# Peripherals.net
KiCad netlist of a schematic drawn in Altium Designer
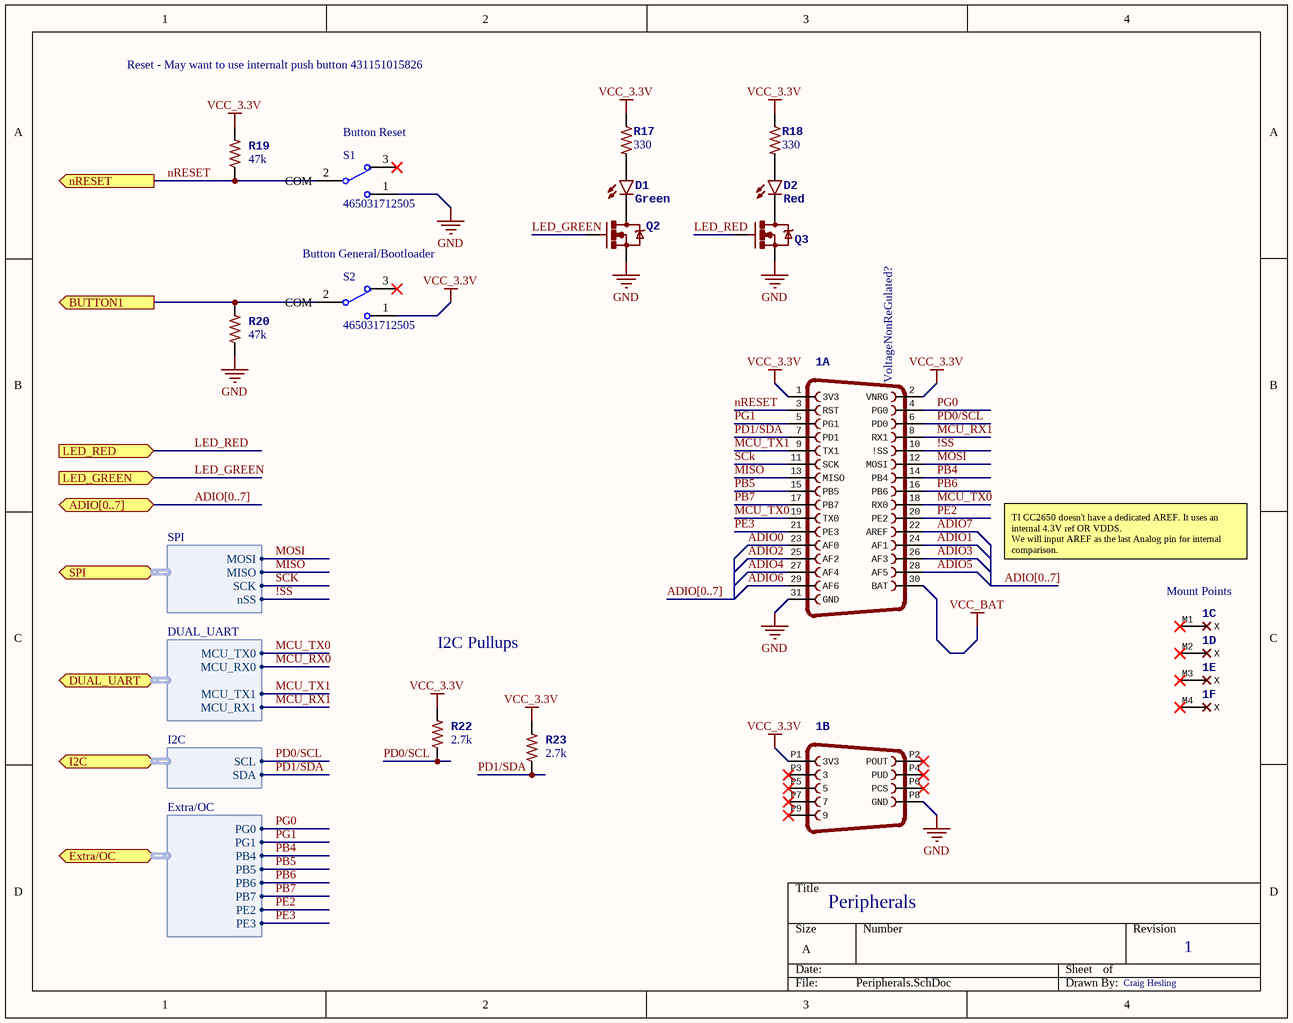
[diagram p0: Peripherals.SchDoc]

(export (version "E")
  (design (tool "Eeschema 10.0.6"))
  (components
    (comp (ref "1")
      (value "Addon Board for Firefly Sensor Nodes    This version is compliant with Firefly Micro powered by Atmel Atmega128RFA1.    Connectors on female gender match those on Firefly Micro Board.    Connectors on male gender mate with Firefly Micro Board. Use these for addons.")
      (footprint "FIREFLY_MICRO_BOARD")
      (libsource (lib "Boards") (part "FIREFLY_MICRO_BOARD"))
    )
    (comp (ref "D1")
      (value "Green")
      (footprint "LED-0603")
      (libsource (lib "SparkFun-LED") (part "LED-GREEN0603"))
    )
    (comp (ref "D2")
      (value "Red")
      (footprint "LED-0603")
      (libsource (lib "SparkFun-LED") (part "LED-RED0603"))
    )
    (comp (ref "Q2")
      (value "Common NMOSFET Parts      MFG P/NStore IDProd ID   FDD8780		TRANS-09984	   SI7820DN		TRANS-11055	   FDS6630A		IC-08089	   2N7002PW		TRANS-11151	   FQP30N06L	  COM-10213	TRANS-10060	   BSS123LT1G		TRANS-08345	   BSS138		TRANS-00830	   BS170			   2N7000")
      (footprint "SOT23-3")
      (libsource (lib "SparkFun-DiscreteSemi") (part "MOSFET-NCHANNELBSS138"))
    )
    (comp (ref "Q3")
      (value "Common NMOSFET Parts      MFG P/NStore IDProd ID   FDD8780		TRANS-09984	   SI7820DN		TRANS-11055	   FDS6630A		IC-08089	   2N7002PW		TRANS-11151	   FQP30N06L	  COM-10213	TRANS-10060	   BSS123LT1G		TRANS-08345	   BSS138		TRANS-00830	   BS170			   2N7000")
      (footprint "SOT23-3")
      (libsource (lib "SparkFun-DiscreteSemi") (part "MOSFET-NCHANNELBSS138"))
    )
    (comp (ref "R17")
      (value "330")
      (footprint "0603-RES")
      (fields (field (name "Comment") "RES-00818"))
      (libsource (lib "SparkFun-Resistors") (part "330OHM1/10W1%(0603)"))
    )
    (comp (ref "R18")
      (value "330")
      (footprint "0603-RES")
      (fields (field (name "Comment") "RES-00818"))
      (libsource (lib "SparkFun-Resistors") (part "330OHM1/10W1%(0603)"))
    )
    (comp (ref "R19")
      (value "47k")
      (footprint "0603-RES")
      (fields (field (name "Comment") "RES-00824"))
      (libsource (lib "SparkFun-Resistors") (part "10KOHM-1/10W-1%(0603)0603"))
    )
    (comp (ref "R20")
      (value "47k")
      (footprint "0603-RES")
      (fields (field (name "Comment") "RES-00824"))
      (libsource (lib "SparkFun-Resistors") (part "10KOHM-1/10W-1%(0603)0603"))
    )
    (comp (ref "R22")
      (value "2.7k")
      (footprint "0603-RES")
      (fields (field (name "Comment") "RES-00824"))
      (libsource (lib "SparkFun-Resistors") (part "10KOHM-1/10W-1%(0603)0603"))
    )
    (comp (ref "R23")
      (value "2.7k")
      (footprint "0603-RES")
      (fields (field (name "Comment") "RES-00824"))
      (libsource (lib "SparkFun-Resistors") (part "10KOHM-1/10W-1%(0603)0603"))
    )
    (comp (ref "S1")
      (value "465031712505")
      (footprint "465031712505")
      (description "WS-PBSU 9.8 x 18.5 mm SMD side push")
      (fields (field (name "MANUFACTURER") "Wurth Elektronik") (field (name "CREATED BY") "Baojun Chen"))
      (libsource (lib "WS-PBSU") (part "WS-PBSU, 465031712505"))
    )
    (comp (ref "S2")
      (value "465031712505")
      (footprint "465031712505")
      (description "WS-PBSU 9.8 x 18.5 mm SMD side push")
      (fields (field (name "MANUFACTURER") "Wurth Elektronik") (field (name "CREATED BY") "Baojun Chen"))
      (libsource (lib "WS-PBSU") (part "WS-PBSU, 465031712505"))
    )
  )
  (nets
    (net (code "5") (name "/!SS") (class "Default")
      (node (ref "1") (pin "10") (pinfunction "!SS_10") (pintype "passive"))
    )
    (net (code "6") (name "/ADIO0") (class "Default")
      (node (ref "1") (pin "23") (pinfunction "AF0_23") (pintype "passive"))
    )
    (net (code "7") (name "/ADIO1") (class "Default")
      (node (ref "1") (pin "24") (pinfunction "AF1_24") (pintype "passive"))
    )
    (net (code "8") (name "/ADIO2") (class "Default")
      (node (ref "1") (pin "25") (pinfunction "AF2_25") (pintype "passive"))
    )
    (net (code "9") (name "/ADIO3") (class "Default")
      (node (ref "1") (pin "26") (pinfunction "AF3_26") (pintype "passive"))
    )
    (net (code "10") (name "/ADIO4") (class "Default")
      (node (ref "1") (pin "27") (pinfunction "AF4_27") (pintype "passive"))
    )
    (net (code "11") (name "/ADIO5") (class "Default")
      (node (ref "1") (pin "28") (pinfunction "AF5_28") (pintype "passive"))
    )
    (net (code "12") (name "/ADIO6") (class "Default")
      (node (ref "1") (pin "29") (pinfunction "AF6_29") (pintype "passive"))
    )
    (net (code "13") (name "/ADIO7") (class "Default")
      (node (ref "1") (pin "22") (pinfunction "AREF_22") (pintype "passive"))
    )
    (net (code "15") (name "/BUTTON1") (class "Default")
      (node (ref "R20") (pin "2") (pinfunction "2_2") (pintype "passive"))
      (node (ref "S2") (pin "2") (pinfunction "COM_2") (pintype "passive"))
    )
    (net (code "16") (name "/LED_GREEN") (class "Default")
      (node (ref "Q2") (pin "1") (pinfunction "G_1") (pintype "passive"))
    )
    (net (code "17") (name "/LED_RED") (class "Default")
      (node (ref "Q3") (pin "1") (pinfunction "G_1") (pintype "passive"))
    )
    (net (code "19") (name "/MCU_RX1") (class "Default")
      (node (ref "1") (pin "8") (pinfunction "RX1_8") (pintype "passive"))
    )
    (net (code "20") (name "/MCU_TX0") (class "Default")
      (node (ref "1") (pin "18") (pinfunction "RX0_18") (pintype "passive"))
      (node (ref "1") (pin "19") (pinfunction "TX0_19") (pintype "passive"))
    )
    (net (code "21") (name "/MCU_TX1") (class "Default")
      (node (ref "1") (pin "9") (pinfunction "TX1_9") (pintype "passive"))
    )
    (net (code "22") (name "/MISO") (class "Default")
      (node (ref "1") (pin "13") (pinfunction "MISO_13") (pintype "passive"))
    )
    (net (code "23") (name "/MOSI") (class "Default")
      (node (ref "1") (pin "12") (pinfunction "MOSI_12") (pintype "passive"))
    )
    (net (code "24") (name "/PB4") (class "Default")
      (node (ref "1") (pin "14") (pinfunction "PB4_14") (pintype "passive"))
    )
    (net (code "25") (name "/PB5") (class "Default")
      (node (ref "1") (pin "15") (pinfunction "PB5_15") (pintype "passive"))
    )
    (net (code "26") (name "/PB6") (class "Default")
      (node (ref "1") (pin "16") (pinfunction "PB6_16") (pintype "passive"))
    )
    (net (code "27") (name "/PB7") (class "Default")
      (node (ref "1") (pin "17") (pinfunction "PB7_17") (pintype "passive"))
    )
    (net (code "28") (name "/PD0{slash}SCL") (class "Default")
      (node (ref "1") (pin "6") (pinfunction "PD0_6") (pintype "passive"))
      (node (ref "R22") (pin "1") (pinfunction "1_1") (pintype "passive"))
    )
    (net (code "29") (name "/PD1{slash}SDA") (class "Default")
      (node (ref "1") (pin "7") (pinfunction "PD1_7") (pintype "passive"))
      (node (ref "R23") (pin "1") (pinfunction "1_1") (pintype "passive"))
    )
    (net (code "30") (name "/PE2") (class "Default")
      (node (ref "1") (pin "20") (pinfunction "PE2_20") (pintype "passive"))
    )
    (net (code "31") (name "/PE3") (class "Default")
      (node (ref "1") (pin "21") (pinfunction "PE3_21") (pintype "passive"))
    )
    (net (code "32") (name "/PG0") (class "Default")
      (node (ref "1") (pin "4") (pinfunction "PG0_4") (pintype "passive"))
    )
    (net (code "33") (name "/PG1") (class "Default")
      (node (ref "1") (pin "5") (pinfunction "PG1_5") (pintype "passive"))
    )
    (net (code "35") (name "/SCk") (class "Default")
      (node (ref "1") (pin "11") (pinfunction "SCK_11") (pintype "passive"))
    )
    (net (code "36") (name "/nRESET") (class "Default")
      (node (ref "1") (pin "3") (pinfunction "RST_3") (pintype "passive"))
      (node (ref "R19") (pin "1") (pinfunction "1_1") (pintype "passive"))
      (node (ref "S1") (pin "2") (pinfunction "COM_2") (pintype "passive"))
    )
    (net (code "41") (name "GND") (class "Default")
      (node (ref "1") (pin "31") (pinfunction "GND_31") (pintype "power_in"))
      (node (ref "1") (pin "P8") (pinfunction "GND_P8") (pintype "power_in"))
      (node (ref "Q2") (pin "2") (pinfunction "S_2") (pintype "passive"))
      (node (ref "Q3") (pin "2") (pinfunction "S_2") (pintype "passive"))
      (node (ref "R20") (pin "1") (pinfunction "1_1") (pintype "passive"))
      (node (ref "S1") (pin "1") (pinfunction "1_1") (pintype "passive"))
    )
    (net (code "42") (name "Net-(D1-PadA)") (class "Default")
      (node (ref "D1") (pin "A") (pinfunction "A_A") (pintype "passive"))
      (node (ref "R17") (pin "2") (pinfunction "2_2") (pintype "passive"))
    )
    (net (code "43") (name "Net-(D2-PadA)") (class "Default")
      (node (ref "D2") (pin "A") (pinfunction "A_A") (pintype "passive"))
      (node (ref "R18") (pin "2") (pinfunction "2_2") (pintype "passive"))
    )
    (net (code "44") (name "Net-(Q2-D)") (class "Default")
      (node (ref "D1") (pin "C") (pinfunction "C_C") (pintype "passive"))
      (node (ref "Q2") (pin "3") (pinfunction "D_3") (pintype "passive"))
    )
    (net (code "45") (name "Net-(Q3-D)") (class "Default")
      (node (ref "D2") (pin "C") (pinfunction "C_C") (pintype "passive"))
      (node (ref "Q3") (pin "3") (pinfunction "D_3") (pintype "passive"))
    )
    (net (code "46") (name "VCC_3.3V") (class "Default")
      (node (ref "1") (pin "1") (pinfunction "3V3_1") (pintype "power_in"))
      (node (ref "1") (pin "2") (pinfunction "VNRG_2") (pintype "power_in"))
      (node (ref "1") (pin "P1") (pinfunction "3V3_P1") (pintype "power_in"))
      (node (ref "R17") (pin "1") (pinfunction "1_1") (pintype "passive"))
      (node (ref "R18") (pin "1") (pinfunction "1_1") (pintype "passive"))
      (node (ref "R19") (pin "2") (pinfunction "2_2") (pintype "passive"))
      (node (ref "R22") (pin "2") (pinfunction "2_2") (pintype "passive"))
      (node (ref "R23") (pin "2") (pinfunction "2_2") (pintype "passive"))
      (node (ref "S2") (pin "1") (pinfunction "1_1") (pintype "passive"))
    )
    (net (code "47") (name "VCC_BAT") (class "Default")
      (node (ref "1") (pin "30") (pinfunction "BAT_30") (pintype "passive"))
    )
    (net (code "48") (name "unconnected-(1B-3-PadP3)") (class "Default")
      (node (ref "1") (pin "P3") (pinfunction "3_P3") (pintype "passive+no_connect"))
    )
    (net (code "49") (name "unconnected-(1B-5-PadP5)") (class "Default")
      (node (ref "1") (pin "P5") (pinfunction "5_P5") (pintype "passive+no_connect"))
    )
    (net (code "50") (name "unconnected-(1B-7-PadP7)") (class "Default")
      (node (ref "1") (pin "P7") (pinfunction "7_P7") (pintype "passive+no_connect"))
    )
    (net (code "51") (name "unconnected-(1B-9-PadP9)") (class "Default")
      (node (ref "1") (pin "P9") (pinfunction "9_P9") (pintype "passive+no_connect"))
    )
    (net (code "52") (name "unconnected-(1B-PCS-PadP6)") (class "Default")
      (node (ref "1") (pin "P6") (pinfunction "PCS_P6") (pintype "passive+no_connect"))
    )
    (net (code "53") (name "unconnected-(1B-POUT-PadP2)") (class "Default")
      (node (ref "1") (pin "P2") (pinfunction "POUT_P2") (pintype "passive+no_connect"))
    )
    (net (code "54") (name "unconnected-(1B-PUD-PadP4)") (class "Default")
      (node (ref "1") (pin "P4") (pinfunction "PUD_P4") (pintype "passive+no_connect"))
    )
    (net (code "55") (name "unconnected-(1C-X-PadM1)") (class "Default")
      (node (ref "1") (pin "M1") (pinfunction "X_M1") (pintype "passive+no_connect"))
    )
    (net (code "56") (name "unconnected-(1D-X-PadM2)") (class "Default")
      (node (ref "1") (pin "M2") (pinfunction "X_M2") (pintype "passive+no_connect"))
    )
    (net (code "57") (name "unconnected-(1E-X-PadM3)") (class "Default")
      (node (ref "1") (pin "M3") (pinfunction "X_M3") (pintype "passive+no_connect"))
    )
    (net (code "58") (name "unconnected-(1F-X-PadM4)") (class "Default")
      (node (ref "1") (pin "M4") (pinfunction "X_M4") (pintype "passive+no_connect"))
    )
    (net (code "59") (name "unconnected-(S1-Pad3)") (class "Default")
      (node (ref "S1") (pin "3") (pinfunction "3_3") (pintype "passive+no_connect"))
    )
    (net (code "60") (name "unconnected-(S2-Pad3)") (class "Default")
      (node (ref "S2") (pin "3") (pinfunction "3_3") (pintype "passive+no_connect"))
    )
  )
)
